# cc2538node.net
KiCad netlist of a schematic drawn in EAGLE
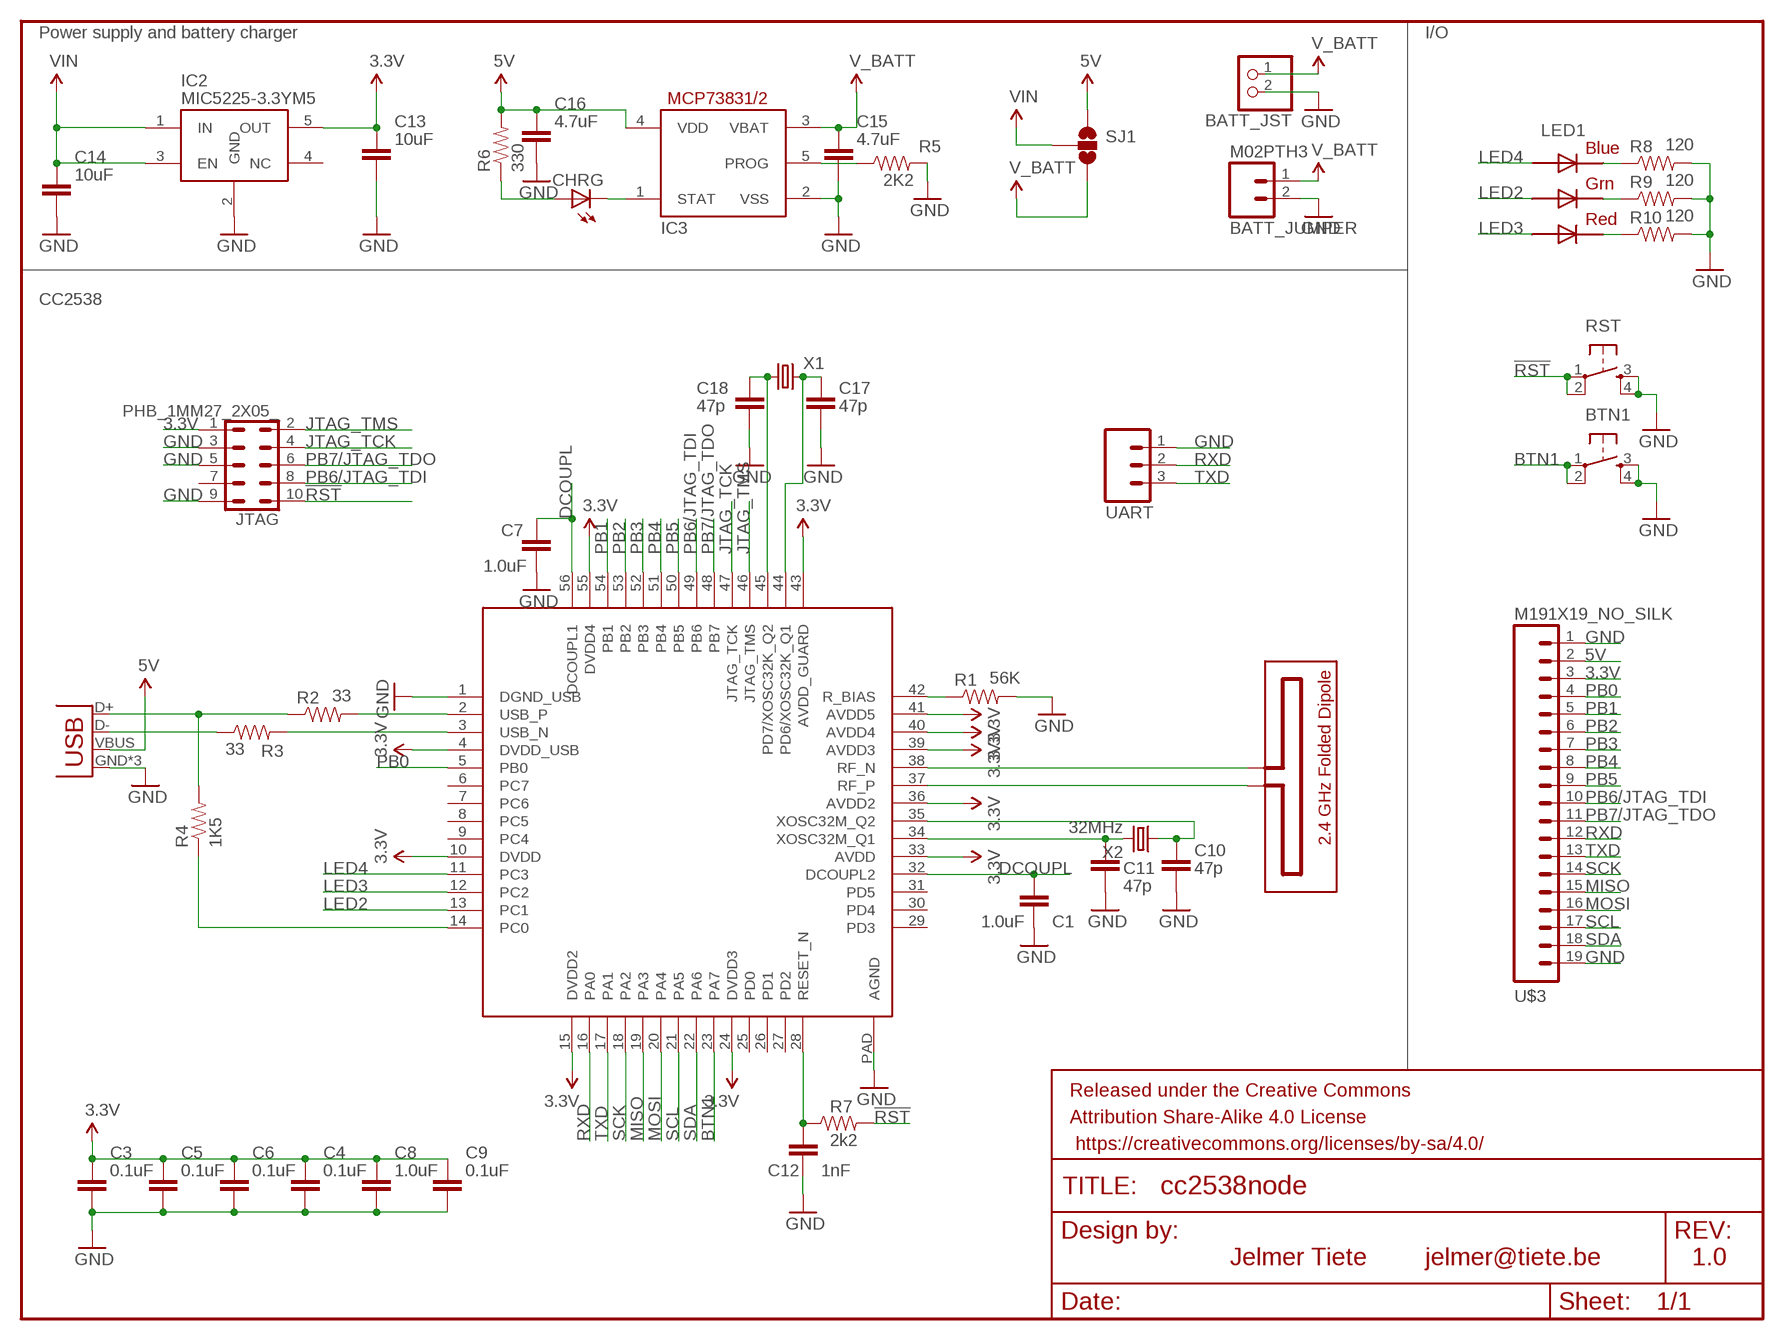
[diagram p0: schematic, sheet 1]

(export (version "E")
  (design (tool "Eeschema 10.0.6"))
  (components
    (comp (ref "BATT_JST")
      (value "JST_2PIN-SMT-RA")
      (footprint "eagle-import:JST-PH-2-SMT-RA")
      (libsource (lib "eagle-import") (part "JST_2PIN-SMT-RA"))
    )
    (comp (ref "BATT_JUMPER")
      (value "M02PTH3")
      (footprint "eagle-import:1X02_LONGPADS")
      (libsource (lib "eagle-import") (part "M02PTH3"))
    )
    (comp (ref "BTN1")
      (value "TAC_SWITCHSMD")
      (footprint "eagle-import:TACTILE_SWITCH_SMD")
      (libsource (lib "eagle-import") (part "TAC_SWITCHSMD"))
    )
    (comp (ref "C1")
      (value "1.0uF")
      (footprint "eagle-import:C603")
      (libsource (lib "eagle-import") (part "CAPACITOR_NPOL-0603"))
    )
    (comp (ref "C3")
      (value "0.1uF")
      (footprint "eagle-import:C603")
      (libsource (lib "eagle-import") (part "CAPACITOR_NPOL-0603"))
    )
    (comp (ref "C4")
      (value "0.1uF")
      (footprint "eagle-import:C603")
      (libsource (lib "eagle-import") (part "CAPACITOR_NPOL-0603"))
    )
    (comp (ref "C5")
      (value "0.1uF")
      (footprint "eagle-import:C603")
      (libsource (lib "eagle-import") (part "CAPACITOR_NPOL-0603"))
    )
    (comp (ref "C6")
      (value "0.1uF")
      (footprint "eagle-import:C603")
      (libsource (lib "eagle-import") (part "CAPACITOR_NPOL-0603"))
    )
    (comp (ref "C7")
      (value "1.0uF")
      (footprint "eagle-import:C603")
      (libsource (lib "eagle-import") (part "CAPACITOR_NPOL-0603"))
    )
    (comp (ref "C8")
      (value "1.0uF")
      (footprint "eagle-import:C603")
      (libsource (lib "eagle-import") (part "CAPACITOR_NPOL-0603"))
    )
    (comp (ref "C9")
      (value "0.1uF")
      (footprint "eagle-import:C603")
      (libsource (lib "eagle-import") (part "CAPACITOR_NPOL-0603"))
    )
    (comp (ref "C10")
      (value "47p")
      (footprint "eagle-import:C603")
      (libsource (lib "eagle-import") (part "CAPACITOR_NPOL-0603"))
    )
    (comp (ref "C11")
      (value "47p")
      (footprint "eagle-import:C603")
      (libsource (lib "eagle-import") (part "CAPACITOR_NPOL-0603"))
    )
    (comp (ref "C12")
      (value "1nF")
      (footprint "eagle-import:C603")
      (libsource (lib "eagle-import") (part "CAPACITOR_NPOL-0603"))
    )
    (comp (ref "C13")
      (value "10uF")
      (footprint "eagle-import:C603")
      (libsource (lib "eagle-import") (part "CAPACITOR_NPOL-0603"))
    )
    (comp (ref "C14")
      (value "10uF")
      (footprint "eagle-import:C603")
      (libsource (lib "eagle-import") (part "CAPACITOR_NPOL-0603"))
    )
    (comp (ref "C15")
      (value "4.7uF")
      (footprint "eagle-import:C603")
      (libsource (lib "eagle-import") (part "CAPACITOR_NPOL-0603"))
    )
    (comp (ref "C16")
      (value "4.7uF")
      (footprint "eagle-import:C603")
      (libsource (lib "eagle-import") (part "CAPACITOR_NPOL-0603"))
    )
    (comp (ref "C17")
      (value "47p")
      (footprint "eagle-import:C603")
      (libsource (lib "eagle-import") (part "CAPACITOR_NPOL-0603"))
    )
    (comp (ref "C18")
      (value "47p")
      (footprint "eagle-import:C603")
      (libsource (lib "eagle-import") (part "CAPACITOR_NPOL-0603"))
    )
    (comp (ref "CHRG")
      (value "LED-0603")
      (footprint "eagle-import:LED-603")
      (libsource (lib "eagle-import") (part "LED-0603"))
    )
    (comp (ref "FRAME2")
      (value "FRAME-LETTER")
      (footprint "eagle-import:CREATIVE_COMMONS")
      (libsource (lib "eagle-import") (part "FRAME-LETTER"))
    )
    (comp (ref "IC1")
      (value "CC2538")
      (footprint "eagle-import:QFN56")
      (libsource (lib "eagle-import") (part "CC2538"))
    )
    (comp (ref "IC2")
      (value "MIC5225-3.3YM5")
      (footprint "eagle-import:SOT23-5")
      (fields (field (name "VOLTAGE") "3.3V"))
      (libsource (lib "eagle-import") (part "MIC5225YM5-3.3"))
    )
    (comp (ref "IC3")
      (value "MCP73831/OT")
      (footprint "eagle-import:SOT23-5L")
      (libsource (lib "eagle-import") (part "MCP73831/OT"))
    )
    (comp (ref "JP1")
      (value "USB-MICROB")
      (footprint "eagle-import:USB-MICROB")
      (libsource (lib "eagle-import") (part "USB-MICROB"))
    )
    (comp (ref "JTAG")
      (value "PHB_1MM27_2X05_")
      (footprint "eagle-import:PHB_1MM27_2X05_SNT_NOSILK")
      (libsource (lib "eagle-import") (part "PHB_1MM27_2X05_"))
    )
    (comp (ref "LED1")
      (value "RGBLED5050")
      (footprint "eagle-import:RGBLED5050")
      (libsource (lib "eagle-import") (part "RGBLED5050"))
    )
    (comp (ref "R1")
      (value "56K")
      (footprint "eagle-import:0805")
      (libsource (lib "eagle-import") (part "RESISTOR0805-RES"))
    )
    (comp (ref "R2")
      (value "33")
      (footprint "eagle-import:0805")
      (libsource (lib "eagle-import") (part "RESISTOR0805-RES"))
    )
    (comp (ref "R3")
      (value "33")
      (footprint "eagle-import:0805")
      (libsource (lib "eagle-import") (part "RESISTOR0805-RES"))
    )
    (comp (ref "R4")
      (value "1K5")
      (footprint "eagle-import:0805")
      (libsource (lib "eagle-import") (part "RESISTOR0805-RES"))
    )
    (comp (ref "R5")
      (value "2K2")
      (footprint "eagle-import:0805")
      (libsource (lib "eagle-import") (part "RESISTOR0805-RES"))
    )
    (comp (ref "R6")
      (value "330")
      (footprint "eagle-import:0805")
      (libsource (lib "eagle-import") (part "RESISTOR0805-RES"))
    )
    (comp (ref "R7")
      (value "2k2")
      (footprint "eagle-import:0805")
      (libsource (lib "eagle-import") (part "RESISTOR0805-RES"))
    )
    (comp (ref "R8")
      (value "120")
      (footprint "eagle-import:0805")
      (libsource (lib "eagle-import") (part "RESISTOR0805-RES"))
    )
    (comp (ref "R9")
      (value "120")
      (footprint "eagle-import:0805")
      (libsource (lib "eagle-import") (part "RESISTOR0805-RES"))
    )
    (comp (ref "R10")
      (value "120")
      (footprint "eagle-import:0805")
      (libsource (lib "eagle-import") (part "RESISTOR0805-RES"))
    )
    (comp (ref "RST")
      (value "TAC_SWITCHSMD")
      (footprint "eagle-import:TACTILE_SWITCH_SMD")
      (libsource (lib "eagle-import") (part "TAC_SWITCHSMD"))
    )
    (comp (ref "SJ1")
      (value "SOLDERJUMPER_2WAYPASTE1&2")
      (footprint "eagle-import:SJ_3_PASTE1&2")
      (libsource (lib "eagle-import") (part "SOLDERJUMPER_2WAYPASTE1&2"))
    )
    (comp (ref "U$1")
      (value "FOLDED_DIPOLE_ANTENNE_2.4")
      (footprint "eagle-import:FOLDED_DIPOLE_2.4")
      (libsource (lib "eagle-import") (part "FOLDED_DIPOLE_ANTENNE_2.4"))
    )
    (comp (ref "U$3")
      (value "M191X19_NO_SILK")
      (footprint "eagle-import:1X19_NO_SILK")
      (libsource (lib "eagle-import") (part "M191X19_NO_SILK"))
    )
    (comp (ref "UART")
      (value "M031X03_NO_SILK")
      (footprint "eagle-import:1X03_NO_SILK")
      (libsource (lib "eagle-import") (part "M031X03_NO_SILK"))
    )
    (comp (ref "X1")
      (value "CRYSTAL32-SMD")
      (footprint "eagle-import:CRYSTAL-32KHZ-SMD")
      (libsource (lib "eagle-import") (part "CRYSTAL32-SMD"))
    )
    (comp (ref "X2")
      (value "32MHz")
      (footprint "eagle-import:CTS406")
      (libsource (lib "eagle-import") (part "CRYSTALCTS406"))
    )
  )
  (nets
    (net (code "1") (name "/BTN1") (class "Default")
      (node (ref "BTN1") (pin "1") (pinfunction "1_1") (pintype "passive"))
      (node (ref "BTN1") (pin "2") (pinfunction "2_2") (pintype "passive"))
      (node (ref "IC1") (pin "23") (pinfunction "PA7_23") (pintype "bidirectional"))
    )
    (net (code "2") (name "/DCOUPL") (class "Default")
      (node (ref "C1") (pin "1") (pinfunction "1_1") (pintype "passive"))
      (node (ref "C7") (pin "1") (pinfunction "1_1") (pintype "passive"))
      (node (ref "IC1") (pin "32") (pinfunction "DCOUPL2_32") (pintype "bidirectional"))
      (node (ref "IC1") (pin "56") (pinfunction "DCOUPL1_56") (pintype "bidirectional"))
    )
    (net (code "3") (name "/JTAG_TCK") (class "Default")
      (node (ref "IC1") (pin "47") (pinfunction "JTAG_TCK_47") (pintype "bidirectional"))
      (node (ref "JTAG") (pin "4") (pinfunction "4_4") (pintype "passive"))
    )
    (net (code "4") (name "/JTAG_TMS") (class "Default")
      (node (ref "IC1") (pin "46") (pinfunction "JTAG_TMS_46") (pintype "bidirectional"))
      (node (ref "JTAG") (pin "2") (pinfunction "2_2") (pintype "passive"))
    )
    (net (code "5") (name "/LED2") (class "Default")
      (node (ref "IC1") (pin "13") (pinfunction "PC1_13") (pintype "bidirectional"))
      (node (ref "LED1") (pin "1") (pinfunction "GREEN_A_1") (pintype "bidirectional"))
    )
    (net (code "6") (name "/LED3") (class "Default")
      (node (ref "IC1") (pin "12") (pinfunction "PC2_12") (pintype "bidirectional"))
      (node (ref "LED1") (pin "2") (pinfunction "RED_A_2") (pintype "bidirectional"))
    )
    (net (code "7") (name "/LED4") (class "Default")
      (node (ref "IC1") (pin "11") (pinfunction "PC3_11") (pintype "bidirectional"))
      (node (ref "LED1") (pin "3") (pinfunction "BLUE_A_3") (pintype "bidirectional"))
    )
    (net (code "8") (name "/MISO") (class "Default")
      (node (ref "IC1") (pin "19") (pinfunction "PA3_19") (pintype "bidirectional"))
      (node (ref "U$3") (pin "15") (pinfunction "15_15") (pintype "passive"))
    )
    (net (code "9") (name "/MOSI") (class "Default")
      (node (ref "IC1") (pin "20") (pinfunction "PA4_20") (pintype "bidirectional"))
      (node (ref "U$3") (pin "16") (pinfunction "16_16") (pintype "passive"))
    )
    (net (code "10") (name "/PB0") (class "Default")
      (node (ref "IC1") (pin "5") (pinfunction "PB0_5") (pintype "bidirectional"))
      (node (ref "U$3") (pin "4") (pinfunction "4_4") (pintype "passive"))
    )
    (net (code "11") (name "/PB1") (class "Default")
      (node (ref "IC1") (pin "54") (pinfunction "PB1_54") (pintype "bidirectional"))
      (node (ref "U$3") (pin "5") (pinfunction "5_5") (pintype "passive"))
    )
    (net (code "12") (name "/PB2") (class "Default")
      (node (ref "IC1") (pin "53") (pinfunction "PB2_53") (pintype "bidirectional"))
      (node (ref "U$3") (pin "6") (pinfunction "6_6") (pintype "passive"))
    )
    (net (code "13") (name "/PB3") (class "Default")
      (node (ref "IC1") (pin "52") (pinfunction "PB3_52") (pintype "bidirectional"))
      (node (ref "U$3") (pin "7") (pinfunction "7_7") (pintype "passive"))
    )
    (net (code "14") (name "/PB4") (class "Default")
      (node (ref "IC1") (pin "51") (pinfunction "PB4_51") (pintype "bidirectional"))
      (node (ref "U$3") (pin "8") (pinfunction "8_8") (pintype "passive"))
    )
    (net (code "15") (name "/PB5") (class "Default")
      (node (ref "IC1") (pin "50") (pinfunction "PB5_50") (pintype "bidirectional"))
      (node (ref "U$3") (pin "9") (pinfunction "9_9") (pintype "passive"))
    )
    (net (code "16") (name "/PB6{slash}JTAG_TDI") (class "Default")
      (node (ref "IC1") (pin "49") (pinfunction "PB6_49") (pintype "bidirectional"))
      (node (ref "JTAG") (pin "8") (pinfunction "8_8") (pintype "passive"))
      (node (ref "U$3") (pin "10") (pinfunction "10_10") (pintype "passive"))
    )
    (net (code "17") (name "/PB7{slash}JTAG_TDO") (class "Default")
      (node (ref "IC1") (pin "48") (pinfunction "PB7_48") (pintype "bidirectional"))
      (node (ref "JTAG") (pin "6") (pinfunction "6_6") (pintype "passive"))
      (node (ref "U$3") (pin "11") (pinfunction "11_11") (pintype "passive"))
    )
    (net (code "18") (name "/RXD") (class "Default")
      (node (ref "IC1") (pin "16") (pinfunction "PA0_16") (pintype "bidirectional"))
      (node (ref "U$3") (pin "12") (pinfunction "12_12") (pintype "passive"))
      (node (ref "UART") (pin "2") (pinfunction "2_2") (pintype "passive"))
    )
    (net (code "19") (name "/SCK") (class "Default")
      (node (ref "IC1") (pin "18") (pinfunction "PA2_18") (pintype "bidirectional"))
      (node (ref "U$3") (pin "14") (pinfunction "14_14") (pintype "passive"))
    )
    (net (code "20") (name "/SCL") (class "Default")
      (node (ref "IC1") (pin "21") (pinfunction "PA5_21") (pintype "bidirectional"))
      (node (ref "U$3") (pin "17") (pinfunction "17_17") (pintype "passive"))
    )
    (net (code "21") (name "/SDA") (class "Default")
      (node (ref "IC1") (pin "22") (pinfunction "PA6_22") (pintype "bidirectional"))
      (node (ref "U$3") (pin "18") (pinfunction "18_18") (pintype "passive"))
    )
    (net (code "22") (name "/TXD") (class "Default")
      (node (ref "IC1") (pin "17") (pinfunction "PA1_17") (pintype "bidirectional"))
      (node (ref "U$3") (pin "13") (pinfunction "13_13") (pintype "passive"))
      (node (ref "UART") (pin "3") (pinfunction "3_3") (pintype "passive"))
    )
    (net (code "23") (name "/~{RST}") (class "Default")
      (node (ref "JTAG") (pin "10") (pinfunction "10_10") (pintype "passive"))
      (node (ref "R7") (pin "2") (pinfunction "2_2") (pintype "passive"))
      (node (ref "RST") (pin "1") (pinfunction "1_1") (pintype "passive"))
      (node (ref "RST") (pin "2") (pinfunction "2_2") (pintype "passive"))
    )
    (net (code "24") (name "3.3V") (class "Default")
      (node (ref "C13") (pin "1") (pinfunction "1_1") (pintype "passive"))
      (node (ref "C3") (pin "1") (pinfunction "1_1") (pintype "passive"))
      (node (ref "C4") (pin "1") (pinfunction "1_1") (pintype "passive"))
      (node (ref "C5") (pin "1") (pinfunction "1_1") (pintype "passive"))
      (node (ref "C6") (pin "1") (pinfunction "1_1") (pintype "passive"))
      (node (ref "C8") (pin "1") (pinfunction "1_1") (pintype "passive"))
      (node (ref "C9") (pin "1") (pinfunction "1_1") (pintype "passive"))
      (node (ref "IC1") (pin "10") (pinfunction "DVDD_10") (pintype "bidirectional"))
      (node (ref "IC1") (pin "15") (pinfunction "DVDD2_15") (pintype "bidirectional"))
      (node (ref "IC1") (pin "24") (pinfunction "DVDD3_24") (pintype "bidirectional"))
      (node (ref "IC1") (pin "33") (pinfunction "AVDD_33") (pintype "bidirectional"))
      (node (ref "IC1") (pin "36") (pinfunction "AVDD2_36") (pintype "bidirectional"))
      (node (ref "IC1") (pin "39") (pinfunction "AVDD3_39") (pintype "bidirectional"))
      (node (ref "IC1") (pin "4") (pinfunction "DVDD_USB_4") (pintype "bidirectional"))
      (node (ref "IC1") (pin "40") (pinfunction "AVDD4_40") (pintype "bidirectional"))
      (node (ref "IC1") (pin "41") (pinfunction "AVDD5_41") (pintype "bidirectional"))
      (node (ref "IC1") (pin "43") (pinfunction "AVDD_GUARD_43") (pintype "bidirectional"))
      (node (ref "IC1") (pin "55") (pinfunction "DVDD4_55") (pintype "bidirectional"))
      (node (ref "IC2") (pin "5") (pinfunction "OUT_5") (pintype "passive"))
      (node (ref "JTAG") (pin "1") (pinfunction "1_1") (pintype "passive"))
      (node (ref "U$3") (pin "3") (pinfunction "3_3") (pintype "passive"))
    )
    (net (code "25") (name "5V") (class "Default")
      (node (ref "C16") (pin "1") (pinfunction "1_1") (pintype "passive"))
      (node (ref "IC3") (pin "4") (pinfunction "VDD_4") (pintype "power_in"))
      (node (ref "JP1") (pin "VBUS") (pinfunction "VBUS_VBUS") (pintype "bidirectional"))
      (node (ref "R6") (pin "2") (pinfunction "2_2") (pintype "passive"))
      (node (ref "SJ1") (pin "1") (pinfunction "1_1") (pintype "passive"))
      (node (ref "U$3") (pin "2") (pinfunction "2_2") (pintype "passive"))
    )
    (net (code "26") (name "GND") (class "Default")
      (node (ref "BATT_JST") (pin "2") (pinfunction "1_2") (pintype "passive"))
      (node (ref "BATT_JUMPER") (pin "2") (pinfunction "2_2") (pintype "passive"))
      (node (ref "BTN1") (pin "3") (pinfunction "3_3") (pintype "passive"))
      (node (ref "BTN1") (pin "4") (pinfunction "4_4") (pintype "passive"))
      (node (ref "C1") (pin "2") (pinfunction "2_2") (pintype "passive"))
      (node (ref "C10") (pin "2") (pinfunction "2_2") (pintype "passive"))
      (node (ref "C11") (pin "2") (pinfunction "2_2") (pintype "passive"))
      (node (ref "C12") (pin "2") (pinfunction "2_2") (pintype "passive"))
      (node (ref "C13") (pin "2") (pinfunction "2_2") (pintype "passive"))
      (node (ref "C14") (pin "2") (pinfunction "2_2") (pintype "passive"))
      (node (ref "C15") (pin "2") (pinfunction "2_2") (pintype "passive"))
      (node (ref "C16") (pin "2") (pinfunction "2_2") (pintype "passive"))
      (node (ref "C17") (pin "2") (pinfunction "2_2") (pintype "passive"))
      (node (ref "C18") (pin "2") (pinfunction "2_2") (pintype "passive"))
      (node (ref "C3") (pin "2") (pinfunction "2_2") (pintype "passive"))
      (node (ref "C4") (pin "2") (pinfunction "2_2") (pintype "passive"))
      (node (ref "C5") (pin "2") (pinfunction "2_2") (pintype "passive"))
      (node (ref "C6") (pin "2") (pinfunction "2_2") (pintype "passive"))
      (node (ref "C7") (pin "2") (pinfunction "2_2") (pintype "passive"))
      (node (ref "C8") (pin "2") (pinfunction "2_2") (pintype "passive"))
      (node (ref "C9") (pin "2") (pinfunction "2_2") (pintype "passive"))
      (node (ref "IC1") (pin "1") (pinfunction "DGND_USB_1") (pintype "bidirectional"))
      (node (ref "IC1") (pin "PAD") (pinfunction "AGND_PAD") (pintype "bidirectional"))
      (node (ref "IC2") (pin "2") (pinfunction "GND_2") (pintype "passive"))
      (node (ref "IC3") (pin "2") (pinfunction "VSS_2") (pintype "power_in"))
      (node (ref "JP1") (pin "GND") (pinfunction "GND_GND") (pintype "bidirectional"))
      (node (ref "JP1") (pin "MT1") (pinfunction "GND_MT1") (pintype "bidirectional"))
      (node (ref "JP1") (pin "MT2") (pinfunction "GND_MT2") (pintype "bidirectional"))
      (node (ref "JTAG") (pin "3") (pinfunction "3_3") (pintype "passive"))
      (node (ref "JTAG") (pin "5") (pinfunction "5_5") (pintype "passive"))
      (node (ref "JTAG") (pin "9") (pinfunction "9_9") (pintype "passive"))
      (node (ref "R1") (pin "2") (pinfunction "2_2") (pintype "passive"))
      (node (ref "R10") (pin "2") (pinfunction "2_2") (pintype "passive"))
      (node (ref "R5") (pin "2") (pinfunction "2_2") (pintype "passive"))
      (node (ref "R8") (pin "2") (pinfunction "2_2") (pintype "passive"))
      (node (ref "R9") (pin "2") (pinfunction "2_2") (pintype "passive"))
      (node (ref "RST") (pin "3") (pinfunction "3_3") (pintype "passive"))
      (node (ref "RST") (pin "4") (pinfunction "4_4") (pintype "passive"))
      (node (ref "U$3") (pin "1") (pinfunction "1_1") (pintype "passive"))
      (node (ref "U$3") (pin "19") (pinfunction "19_19") (pintype "passive"))
      (node (ref "UART") (pin "1") (pinfunction "1_1") (pintype "passive"))
    )
    (net (code "27") (name "Net-(CHRG-PadA)") (class "Default")
      (node (ref "CHRG") (pin "A") (pinfunction "A_A") (pintype "passive"))
      (node (ref "R6") (pin "1") (pinfunction "1_1") (pintype "passive"))
    )
    (net (code "28") (name "Net-(IC1-PC0)") (class "Default")
      (node (ref "IC1") (pin "14") (pinfunction "PC0_14") (pintype "bidirectional"))
      (node (ref "R4") (pin "1") (pinfunction "1_1") (pintype "passive"))
    )
    (net (code "29") (name "Net-(IC1-PD6{slash}XOSC32K_Q1)") (class "Default")
      (node (ref "C17") (pin "1") (pinfunction "1_1") (pintype "passive"))
      (node (ref "IC1") (pin "44") (pinfunction "PD6/XOSC32K_Q1_44") (pintype "bidirectional"))
      (node (ref "X1") (pin "X2") (pinfunction "2_X2") (pintype "passive"))
    )
    (net (code "30") (name "Net-(IC1-PD7{slash}XOSC32K_Q2)") (class "Default")
      (node (ref "C18") (pin "1") (pinfunction "1_1") (pintype "passive"))
      (node (ref "IC1") (pin "45") (pinfunction "PD7/XOSC32K_Q2_45") (pintype "bidirectional"))
      (node (ref "X1") (pin "X1") (pinfunction "1_X1") (pintype "passive"))
    )
    (net (code "31") (name "Net-(IC1-RESET_N)") (class "Default")
      (node (ref "C12") (pin "1") (pinfunction "1_1") (pintype "passive"))
      (node (ref "IC1") (pin "28") (pinfunction "RESET_N_28") (pintype "bidirectional"))
      (node (ref "R7") (pin "1") (pinfunction "1_1") (pintype "passive"))
    )
    (net (code "32") (name "Net-(IC1-RF_N)") (class "Default")
      (node (ref "IC1") (pin "38") (pinfunction "RF_N_38") (pintype "bidirectional"))
      (node (ref "U$1") (pin "P$1") (pinfunction "P$1_P$1") (pintype "bidirectional"))
    )
    (net (code "33") (name "Net-(IC1-RF_P)") (class "Default")
      (node (ref "IC1") (pin "37") (pinfunction "RF_P_37") (pintype "bidirectional"))
      (node (ref "U$1") (pin "P$2") (pinfunction "P$2_P$2") (pintype "bidirectional"))
    )
    (net (code "34") (name "Net-(IC1-R_BIAS)") (class "Default")
      (node (ref "IC1") (pin "42") (pinfunction "R_BIAS_42") (pintype "bidirectional"))
      (node (ref "R1") (pin "1") (pinfunction "1_1") (pintype "passive"))
    )
    (net (code "35") (name "Net-(IC1-USB_N)") (class "Default")
      (node (ref "IC1") (pin "3") (pinfunction "USB_N_3") (pintype "bidirectional"))
      (node (ref "R3") (pin "2") (pinfunction "2_2") (pintype "passive"))
    )
    (net (code "36") (name "Net-(IC1-USB_P)") (class "Default")
      (node (ref "IC1") (pin "2") (pinfunction "USB_P_2") (pintype "bidirectional"))
      (node (ref "R2") (pin "2") (pinfunction "2_2") (pintype "passive"))
    )
    (net (code "37") (name "Net-(IC1-XOSC32M_Q1)") (class "Default")
      (node (ref "C11") (pin "1") (pinfunction "1_1") (pintype "passive"))
      (node (ref "IC1") (pin "34") (pinfunction "XOSC32M_Q1_34") (pintype "bidirectional"))
      (node (ref "X2") (pin "3") (pinfunction "2_3") (pintype "passive"))
    )
    (net (code "38") (name "Net-(IC1-XOSC32M_Q2)") (class "Default")
      (node (ref "C10") (pin "1") (pinfunction "1_1") (pintype "passive"))
      (node (ref "IC1") (pin "35") (pinfunction "XOSC32M_Q2_35") (pintype "bidirectional"))
      (node (ref "X2") (pin "1") (pinfunction "1_1") (pintype "passive"))
    )
    (net (code "39") (name "Net-(IC3-PROG)") (class "Default")
      (node (ref "IC3") (pin "5") (pinfunction "PROG_5") (pintype "input"))
      (node (ref "R5") (pin "1") (pinfunction "1_1") (pintype "passive"))
    )
    (net (code "40") (name "Net-(IC3-STAT)") (class "Default")
      (node (ref "CHRG") (pin "C") (pinfunction "C_C") (pintype "passive"))
      (node (ref "IC3") (pin "1") (pinfunction "STAT_1") (pintype "output"))
    )
    (net (code "41") (name "Net-(JP1-PadD+)") (class "Default")
      (node (ref "JP1") (pin "D+") (pinfunction "D+_D+") (pintype "bidirectional"))
      (node (ref "R2") (pin "1") (pinfunction "1_1") (pintype "passive"))
      (node (ref "R4") (pin "2") (pinfunction "2_2") (pintype "passive"))
    )
    (net (code "42") (name "Net-(JP1-PadD-)") (class "Default")
      (node (ref "JP1") (pin "D-") (pinfunction "D-_D-") (pintype "bidirectional"))
      (node (ref "R3") (pin "1") (pinfunction "1_1") (pintype "passive"))
    )
    (net (code "43") (name "Net-(LED1-BLUE_C)") (class "Default")
      (node (ref "LED1") (pin "4") (pinfunction "BLUE_C_4") (pintype "bidirectional"))
      (node (ref "R8") (pin "1") (pinfunction "1_1") (pintype "passive"))
    )
    (net (code "44") (name "Net-(LED1-GREEN_C)") (class "Default")
      (node (ref "LED1") (pin "6") (pinfunction "GREEN_C_6") (pintype "bidirectional"))
      (node (ref "R9") (pin "1") (pinfunction "1_1") (pintype "passive"))
    )
    (net (code "45") (name "Net-(LED1-RED_C)") (class "Default")
      (node (ref "LED1") (pin "5") (pinfunction "RED_C_5") (pintype "bidirectional"))
      (node (ref "R10") (pin "1") (pinfunction "1_1") (pintype "passive"))
    )
    (net (code "46") (name "VIN") (class "Default")
      (node (ref "C14") (pin "1") (pinfunction "1_1") (pintype "passive"))
      (node (ref "IC2") (pin "1") (pinfunction "IN_1") (pintype "passive"))
      (node (ref "IC2") (pin "3") (pinfunction "EN_3") (pintype "input"))
      (node (ref "SJ1") (pin "2") (pinfunction "2_2") (pintype "passive"))
    )
    (net (code "47") (name "V_BATT") (class "Default")
      (node (ref "BATT_JST") (pin "1") (pinfunction "2_1") (pintype "passive"))
      (node (ref "BATT_JUMPER") (pin "1") (pinfunction "1_1") (pintype "passive"))
      (node (ref "C15") (pin "1") (pinfunction "1_1") (pintype "passive"))
      (node (ref "IC3") (pin "3") (pinfunction "VBAT_3") (pintype "bidirectional"))
      (node (ref "SJ1") (pin "3") (pinfunction "3_3") (pintype "passive"))
    )
    (net (code "48") (name "unconnected-(IC1-PC4-Pad9)") (class "Default")
      (node (ref "IC1") (pin "9") (pinfunction "PC4_9") (pintype "bidirectional"))
    )
    (net (code "49") (name "unconnected-(IC1-PC5-Pad8)") (class "Default")
      (node (ref "IC1") (pin "8") (pinfunction "PC5_8") (pintype "bidirectional"))
    )
    (net (code "50") (name "unconnected-(IC1-PC6-Pad7)") (class "Default")
      (node (ref "IC1") (pin "7") (pinfunction "PC6_7") (pintype "bidirectional"))
    )
    (net (code "51") (name "unconnected-(IC1-PC7-Pad6)") (class "Default")
      (node (ref "IC1") (pin "6") (pinfunction "PC7_6") (pintype "bidirectional"))
    )
    (net (code "52") (name "unconnected-(IC1-PD0-Pad25)") (class "Default")
      (node (ref "IC1") (pin "25") (pinfunction "PD0_25") (pintype "bidirectional"))
    )
    (net (code "53") (name "unconnected-(IC1-PD1-Pad26)") (class "Default")
      (node (ref "IC1") (pin "26") (pinfunction "PD1_26") (pintype "bidirectional"))
    )
    (net (code "54") (name "unconnected-(IC1-PD2-Pad27)") (class "Default")
      (node (ref "IC1") (pin "27") (pinfunction "PD2_27") (pintype "bidirectional"))
    )
    (net (code "55") (name "unconnected-(IC1-PD3-Pad29)") (class "Default")
      (node (ref "IC1") (pin "29") (pinfunction "PD3_29") (pintype "bidirectional"))
    )
    (net (code "56") (name "unconnected-(IC1-PD4-Pad30)") (class "Default")
      (node (ref "IC1") (pin "30") (pinfunction "PD4_30") (pintype "bidirectional"))
    )
    (net (code "57") (name "unconnected-(IC1-PD5-Pad31)") (class "Default")
      (node (ref "IC1") (pin "31") (pinfunction "PD5_31") (pintype "bidirectional"))
    )
    (net (code "58") (name "unconnected-(IC2-NC-Pad4)") (class "Default")
      (node (ref "IC2") (pin "4") (pinfunction "NC_4") (pintype "no_connect"))
    )
    (net (code "59") (name "unconnected-(JTAG-Pad7)") (class "Default")
      (node (ref "JTAG") (pin "7") (pinfunction "7_7") (pintype "passive"))
    )
  )
)
